# AnalogPairCommon.net
KiCad netlist of a schematic drawn in EAGLE
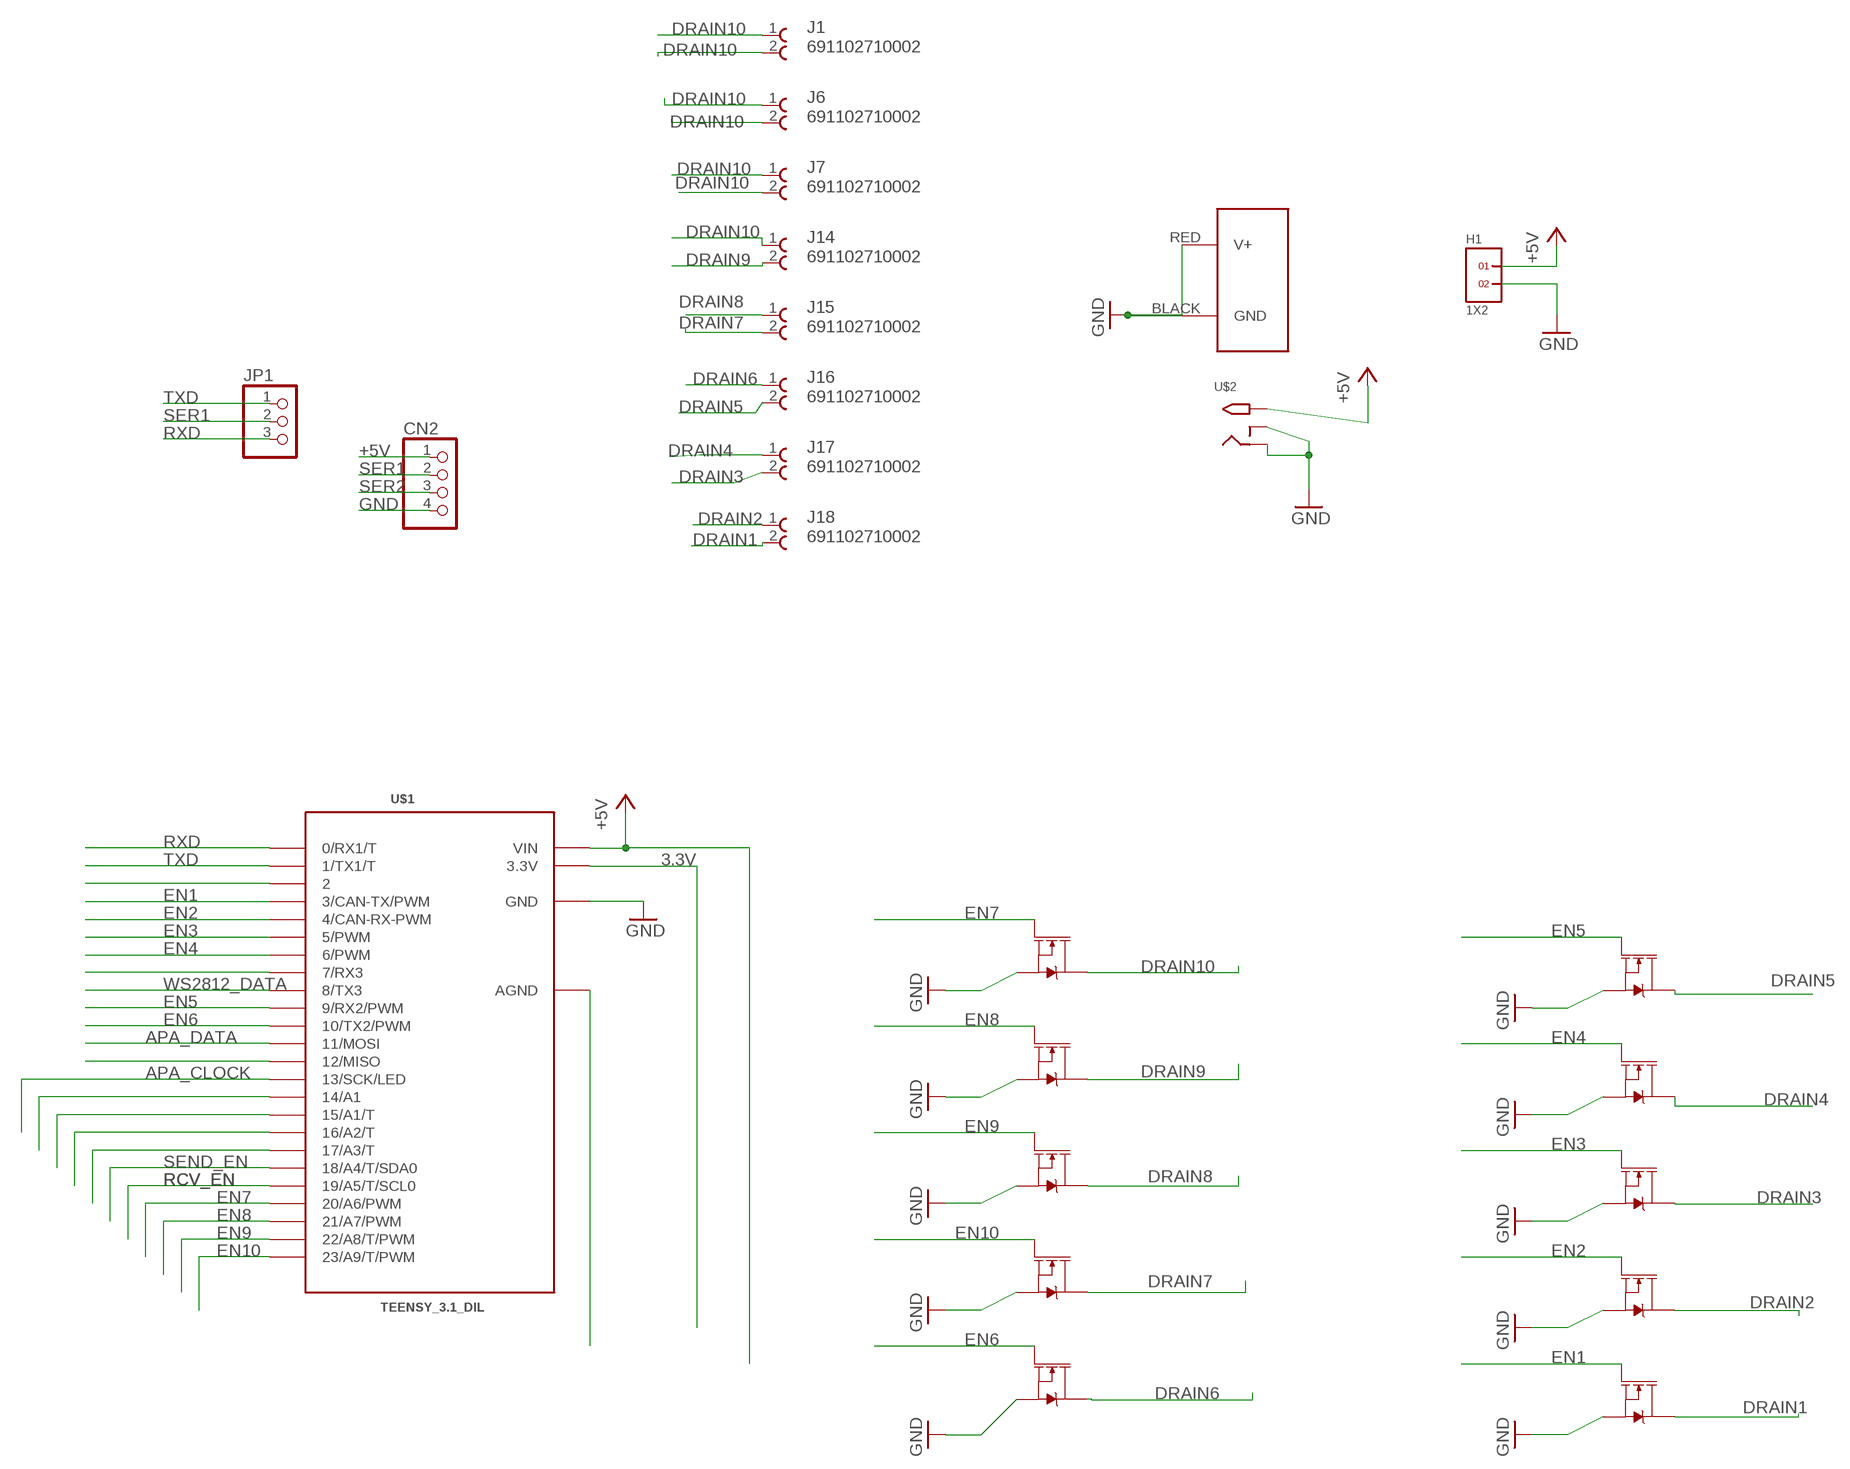
[diagram p0: schematic, sheet 1]

(export (version "E")
  (design (tool "Eeschema 10.0.6"))
  (components
    (comp (ref "CN2")
      (value "HEADER-1X4")
      (footprint "eagle-import:1X04_OVAL")
      (libsource (lib "eagle-import") (part "HEADER-1X4"))
    )
    (comp (ref "H1")
      (value "1X2")
      (footprint "eagle-import:1X2")
      (libsource (lib "eagle-import") (part "1X2"))
    )
    (comp (ref "J1")
      (value "691102710002")
      (footprint "eagle-import:691102710002")
      (fields (field (name "MF") "Wurth Electronics"))
      (libsource (lib "eagle-import") (part "691102710002"))
    )
    (comp (ref "J2")
      (value "POWERPOLE_POWER25A")
      (footprint "eagle-import:POWERPOLE_PAIR_25A")
      (libsource (lib "eagle-import") (part "POWERPOLE_POWER25A"))
    )
    (comp (ref "J6")
      (value "691102710002")
      (footprint "eagle-import:691102710002")
      (fields (field (name "MF") "Wurth Electronics"))
      (libsource (lib "eagle-import") (part "691102710002"))
    )
    (comp (ref "J7")
      (value "691102710002")
      (footprint "eagle-import:691102710002")
      (fields (field (name "MF") "Wurth Electronics"))
      (libsource (lib "eagle-import") (part "691102710002"))
    )
    (comp (ref "J14")
      (value "691102710002")
      (footprint "eagle-import:691102710002")
      (fields (field (name "MF") "Wurth Electronics"))
      (libsource (lib "eagle-import") (part "691102710002"))
    )
    (comp (ref "J15")
      (value "691102710002")
      (footprint "eagle-import:691102710002")
      (fields (field (name "MF") "Wurth Electronics"))
      (libsource (lib "eagle-import") (part "691102710002"))
    )
    (comp (ref "J16")
      (value "691102710002")
      (footprint "eagle-import:691102710002")
      (fields (field (name "MF") "Wurth Electronics"))
      (libsource (lib "eagle-import") (part "691102710002"))
    )
    (comp (ref "J17")
      (value "691102710002")
      (footprint "eagle-import:691102710002")
      (fields (field (name "MF") "Wurth Electronics"))
      (libsource (lib "eagle-import") (part "691102710002"))
    )
    (comp (ref "J18")
      (value "691102710002")
      (footprint "eagle-import:691102710002")
      (fields (field (name "MF") "Wurth Electronics"))
      (libsource (lib "eagle-import") (part "691102710002"))
    )
    (comp (ref "JP1")
      (value "PINHD-1X3")
      (footprint "eagle-import:1X03")
      (libsource (lib "eagle-import") (part "PINHD-1X3"))
    )
    (comp (ref "Q1")
      (value "35A/25V/8.5mΩ")
      (footprint "eagle-import:DPAK")
      (libsource (lib "eagle-import") (part "MOSFET-NCH-FDD8780"))
    )
    (comp (ref "Q2")
      (value "35A/25V/8.5mΩ")
      (footprint "eagle-import:DPAK")
      (libsource (lib "eagle-import") (part "MOSFET-NCH-FDD8780"))
    )
    (comp (ref "Q3")
      (value "35A/25V/8.5mΩ")
      (footprint "eagle-import:DPAK")
      (libsource (lib "eagle-import") (part "MOSFET-NCH-FDD8780"))
    )
    (comp (ref "Q4")
      (value "35A/25V/8.5mΩ")
      (footprint "eagle-import:DPAK")
      (libsource (lib "eagle-import") (part "MOSFET-NCH-FDD8780"))
    )
    (comp (ref "Q5")
      (value "35A/25V/8.5mΩ")
      (footprint "eagle-import:DPAK")
      (libsource (lib "eagle-import") (part "MOSFET-NCH-FDD8780"))
    )
    (comp (ref "Q6")
      (value "35A/25V/8.5mΩ")
      (footprint "eagle-import:DPAK")
      (libsource (lib "eagle-import") (part "MOSFET-NCH-FDD8780"))
    )
    (comp (ref "Q7")
      (value "35A/25V/8.5mΩ")
      (footprint "eagle-import:DPAK")
      (libsource (lib "eagle-import") (part "MOSFET-NCH-FDD8780"))
    )
    (comp (ref "Q8")
      (value "35A/25V/8.5mΩ")
      (footprint "eagle-import:DPAK")
      (libsource (lib "eagle-import") (part "MOSFET-NCH-FDD8780"))
    )
    (comp (ref "Q9")
      (value "35A/25V/8.5mΩ")
      (footprint "eagle-import:DPAK")
      (libsource (lib "eagle-import") (part "MOSFET-NCH-FDD8780"))
    )
    (comp (ref "Q10")
      (value "35A/25V/8.5mΩ")
      (footprint "eagle-import:DPAK")
      (libsource (lib "eagle-import") (part "MOSFET-NCH-FDD8780"))
    )
    (comp (ref "U$1")
      (value "TEENSY_3.1_DIL")
      (footprint "eagle-import:TEENSY3-DIL")
      (libsource (lib "eagle-import") (part "TEENSY_3.1_DIL"))
    )
    (comp (ref "U$2")
      (value "2.1MMJACKTHM")
      (footprint "eagle-import:PJ-102A")
      (libsource (lib "eagle-import") (part "2.1MMJACKTHM"))
    )
  )
  (nets
    (net (code "1") (name "+5V") (class "Default")
      (node (ref "CN2") (pin "1") (pinfunction "1_1") (pintype "passive"))
      (node (ref "H1") (pin "1") (pinfunction "1_1") (pintype "bidirectional"))
      (node (ref "U$1") (pin "VIN") (pinfunction "VIN_VIN") (pintype "power_in"))
      (node (ref "U$2") (pin "TIP") (pinfunction "TIP_TIP") (pintype "bidirectional"))
    )
    (net (code "2") (name "/3.3V") (class "Default")
      (node (ref "U$1") (pin "3.3V") (pinfunction "3.3V_3.3V") (pintype "power_in"))
    )
    (net (code "3") (name "/APA_CLOCK") (class "Default")
      (node (ref "U$1") (pin "13") (pinfunction "13/SCK/LED_13") (pintype "bidirectional"))
    )
    (net (code "4") (name "/APA_DATA") (class "Default")
      (node (ref "U$1") (pin "11") (pinfunction "11/MOSI_11") (pintype "bidirectional"))
    )
    (net (code "5") (name "/DRAIN1") (class "Default")
      (node (ref "J18") (pin "2") (pinfunction "2_2") (pintype "passive"))
      (node (ref "Q10") (pin "4") (pinfunction "D_4") (pintype "bidirectional"))
    )
    (net (code "6") (name "/DRAIN2") (class "Default")
      (node (ref "J18") (pin "1") (pinfunction "1_1") (pintype "passive"))
      (node (ref "Q9") (pin "4") (pinfunction "D_4") (pintype "bidirectional"))
    )
    (net (code "7") (name "/DRAIN3") (class "Default")
      (node (ref "J17") (pin "2") (pinfunction "2_2") (pintype "passive"))
      (node (ref "Q8") (pin "4") (pinfunction "D_4") (pintype "bidirectional"))
    )
    (net (code "8") (name "/DRAIN4") (class "Default")
      (node (ref "J17") (pin "1") (pinfunction "1_1") (pintype "passive"))
      (node (ref "Q7") (pin "4") (pinfunction "D_4") (pintype "bidirectional"))
    )
    (net (code "9") (name "/DRAIN5") (class "Default")
      (node (ref "J16") (pin "2") (pinfunction "2_2") (pintype "passive"))
      (node (ref "Q4") (pin "4") (pinfunction "D_4") (pintype "bidirectional"))
    )
    (net (code "10") (name "/DRAIN6") (class "Default")
      (node (ref "J16") (pin "1") (pinfunction "1_1") (pintype "passive"))
      (node (ref "Q2") (pin "4") (pinfunction "D_4") (pintype "bidirectional"))
    )
    (net (code "11") (name "/DRAIN7") (class "Default")
      (node (ref "J15") (pin "2") (pinfunction "2_2") (pintype "passive"))
      (node (ref "Q6") (pin "4") (pinfunction "D_4") (pintype "bidirectional"))
    )
    (net (code "12") (name "/DRAIN8") (class "Default")
      (node (ref "J15") (pin "1") (pinfunction "1_1") (pintype "passive"))
      (node (ref "Q5") (pin "4") (pinfunction "D_4") (pintype "bidirectional"))
    )
    (net (code "13") (name "/DRAIN9") (class "Default")
      (node (ref "J14") (pin "2") (pinfunction "2_2") (pintype "passive"))
      (node (ref "Q3") (pin "4") (pinfunction "D_4") (pintype "bidirectional"))
    )
    (net (code "14") (name "/DRAIN10") (class "Default")
      (node (ref "J1") (pin "1") (pinfunction "1_1") (pintype "passive"))
      (node (ref "J1") (pin "2") (pinfunction "2_2") (pintype "passive"))
      (node (ref "J14") (pin "1") (pinfunction "1_1") (pintype "passive"))
      (node (ref "J6") (pin "1") (pinfunction "1_1") (pintype "passive"))
      (node (ref "J6") (pin "2") (pinfunction "2_2") (pintype "passive"))
      (node (ref "J7") (pin "1") (pinfunction "1_1") (pintype "passive"))
      (node (ref "J7") (pin "2") (pinfunction "2_2") (pintype "passive"))
      (node (ref "Q1") (pin "4") (pinfunction "D_4") (pintype "bidirectional"))
    )
    (net (code "15") (name "/EN1") (class "Default")
      (node (ref "Q10") (pin "1") (pinfunction "G_1") (pintype "bidirectional"))
      (node (ref "U$1") (pin "3") (pinfunction "3/CAN-TX/PWM_3") (pintype "bidirectional"))
    )
    (net (code "16") (name "/EN2") (class "Default")
      (node (ref "Q9") (pin "1") (pinfunction "G_1") (pintype "bidirectional"))
      (node (ref "U$1") (pin "4") (pinfunction "4/CAN-RX-PWM_4") (pintype "bidirectional"))
    )
    (net (code "17") (name "/EN3") (class "Default")
      (node (ref "Q8") (pin "1") (pinfunction "G_1") (pintype "bidirectional"))
      (node (ref "U$1") (pin "5") (pinfunction "5/PWM_5") (pintype "bidirectional"))
    )
    (net (code "18") (name "/EN4") (class "Default")
      (node (ref "Q7") (pin "1") (pinfunction "G_1") (pintype "bidirectional"))
      (node (ref "U$1") (pin "6") (pinfunction "6/PWM_6") (pintype "bidirectional"))
    )
    (net (code "19") (name "/EN5") (class "Default")
      (node (ref "Q4") (pin "1") (pinfunction "G_1") (pintype "bidirectional"))
      (node (ref "U$1") (pin "9") (pinfunction "9/RX2/PWM_9") (pintype "bidirectional"))
    )
    (net (code "20") (name "/EN6") (class "Default")
      (node (ref "Q2") (pin "1") (pinfunction "G_1") (pintype "bidirectional"))
      (node (ref "U$1") (pin "10") (pinfunction "10/TX2/PWM_10") (pintype "bidirectional"))
    )
    (net (code "21") (name "/EN7") (class "Default")
      (node (ref "Q1") (pin "1") (pinfunction "G_1") (pintype "bidirectional"))
      (node (ref "U$1") (pin "20/A6") (pinfunction "20/A6/PWM_20/A6") (pintype "bidirectional"))
    )
    (net (code "22") (name "/EN8") (class "Default")
      (node (ref "Q3") (pin "1") (pinfunction "G_1") (pintype "bidirectional"))
      (node (ref "U$1") (pin "21/A7") (pinfunction "21/A7/PWM_21/A7") (pintype "bidirectional"))
    )
    (net (code "23") (name "/EN9") (class "Default")
      (node (ref "Q5") (pin "1") (pinfunction "G_1") (pintype "bidirectional"))
      (node (ref "U$1") (pin "22/A8") (pinfunction "22/A8/T/PWM_22/A8") (pintype "bidirectional"))
    )
    (net (code "24") (name "/EN10") (class "Default")
      (node (ref "Q6") (pin "1") (pinfunction "G_1") (pintype "bidirectional"))
      (node (ref "U$1") (pin "23/A9") (pinfunction "23/A9/T/PWM_23/A9") (pintype "bidirectional"))
    )
    (net (code "25") (name "/RCV_EN") (class "Default")
      (node (ref "U$1") (pin "19/A5") (pinfunction "19/A5/T/SCL0_19/A5") (pintype "bidirectional"))
    )
    (net (code "26") (name "/RXD") (class "Default")
      (node (ref "JP1") (pin "3") (pinfunction "3_3") (pintype "passive"))
      (node (ref "U$1") (pin "0") (pinfunction "0/RX1/T_0") (pintype "bidirectional"))
    )
    (net (code "27") (name "/SEND_EN") (class "Default")
      (node (ref "U$1") (pin "18/A4") (pinfunction "18/A4/T/SDA0_18/A4") (pintype "bidirectional"))
    )
    (net (code "28") (name "/SER1") (class "Default")
      (node (ref "CN2") (pin "2") (pinfunction "2_2") (pintype "passive"))
      (node (ref "JP1") (pin "2") (pinfunction "2_2") (pintype "passive"))
    )
    (net (code "29") (name "/SER2") (class "Default")
      (node (ref "CN2") (pin "3") (pinfunction "3_3") (pintype "passive"))
    )
    (net (code "30") (name "/TXD") (class "Default")
      (node (ref "JP1") (pin "1") (pinfunction "1_1") (pintype "passive"))
      (node (ref "U$1") (pin "1") (pinfunction "1/TX1/T_1") (pintype "bidirectional"))
    )
    (net (code "31") (name "/WS2812_DATA") (class "Default")
      (node (ref "U$1") (pin "8") (pinfunction "8/TX3_8") (pintype "bidirectional"))
    )
    (net (code "32") (name "GND") (class "Default")
      (node (ref "CN2") (pin "4") (pinfunction "4_4") (pintype "passive"))
      (node (ref "H1") (pin "2") (pinfunction "2_2") (pintype "bidirectional"))
      (node (ref "J2") (pin "BLACK") (pinfunction "GND_BLACK") (pintype "power_in"))
      (node (ref "J2") (pin "RED") (pinfunction "V+_RED") (pintype "power_in"))
      (node (ref "Q1") (pin "3") (pinfunction "S_3") (pintype "bidirectional"))
      (node (ref "Q10") (pin "3") (pinfunction "S_3") (pintype "bidirectional"))
      (node (ref "Q2") (pin "3") (pinfunction "S_3") (pintype "bidirectional"))
      (node (ref "Q3") (pin "3") (pinfunction "S_3") (pintype "bidirectional"))
      (node (ref "Q4") (pin "3") (pinfunction "S_3") (pintype "bidirectional"))
      (node (ref "Q5") (pin "3") (pinfunction "S_3") (pintype "bidirectional"))
      (node (ref "Q6") (pin "3") (pinfunction "S_3") (pintype "bidirectional"))
      (node (ref "Q7") (pin "3") (pinfunction "S_3") (pintype "bidirectional"))
      (node (ref "Q8") (pin "3") (pinfunction "S_3") (pintype "bidirectional"))
      (node (ref "Q9") (pin "3") (pinfunction "S_3") (pintype "bidirectional"))
      (node (ref "U$1") (pin "GND") (pinfunction "GND_GND") (pintype "power_in"))
      (node (ref "U$2") (pin "RING") (pinfunction "RING_RING") (pintype "bidirectional"))
      (node (ref "U$2") (pin "RING_SW") (pinfunction "RING_SW_RING_SW") (pintype "bidirectional"))
    )
    (net (code "33") (name "unconnected-(U$1-7{slash}RX3-Pad7)") (class "Default")
      (node (ref "U$1") (pin "7") (pinfunction "7/RX3_7") (pintype "bidirectional"))
    )
    (net (code "34") (name "unconnected-(U$1-12{slash}MISO-Pad12)") (class "Default")
      (node (ref "U$1") (pin "12") (pinfunction "12/MISO_12") (pintype "bidirectional"))
    )
    (net (code "35") (name "unconnected-(U$1-14{slash}A1-Pad14{slash}A0)") (class "Default")
      (node (ref "U$1") (pin "14/A0") (pinfunction "14/A1_14/A0") (pintype "bidirectional"))
    )
    (net (code "36") (name "unconnected-(U$1-15{slash}A1{slash}T-Pad15{slash}A1)") (class "Default")
      (node (ref "U$1") (pin "15/A1") (pinfunction "15/A1/T_15/A1") (pintype "bidirectional"))
    )
    (net (code "37") (name "unconnected-(U$1-16{slash}A2{slash}T-Pad16{slash}A2)") (class "Default")
      (node (ref "U$1") (pin "16/A2") (pinfunction "16/A2/T_16/A2") (pintype "bidirectional"))
    )
    (net (code "38") (name "unconnected-(U$1-17{slash}A3{slash}T-Pad17{slash}A3)") (class "Default")
      (node (ref "U$1") (pin "17/A3") (pinfunction "17/A3/T_17/A3") (pintype "bidirectional"))
    )
    (net (code "39") (name "unconnected-(U$1-Pad2)") (class "Default")
      (node (ref "U$1") (pin "2") (pinfunction "2_2") (pintype "bidirectional"))
    )
    (net (code "40") (name "unconnected-(U$1-PadAGND)") (class "Default")
      (node (ref "U$1") (pin "AGND") (pinfunction "AGND_AGND") (pintype "power_in"))
    )
  )
)
